# Connectors.net
KiCad netlist of a schematic drawn in Altium Designer
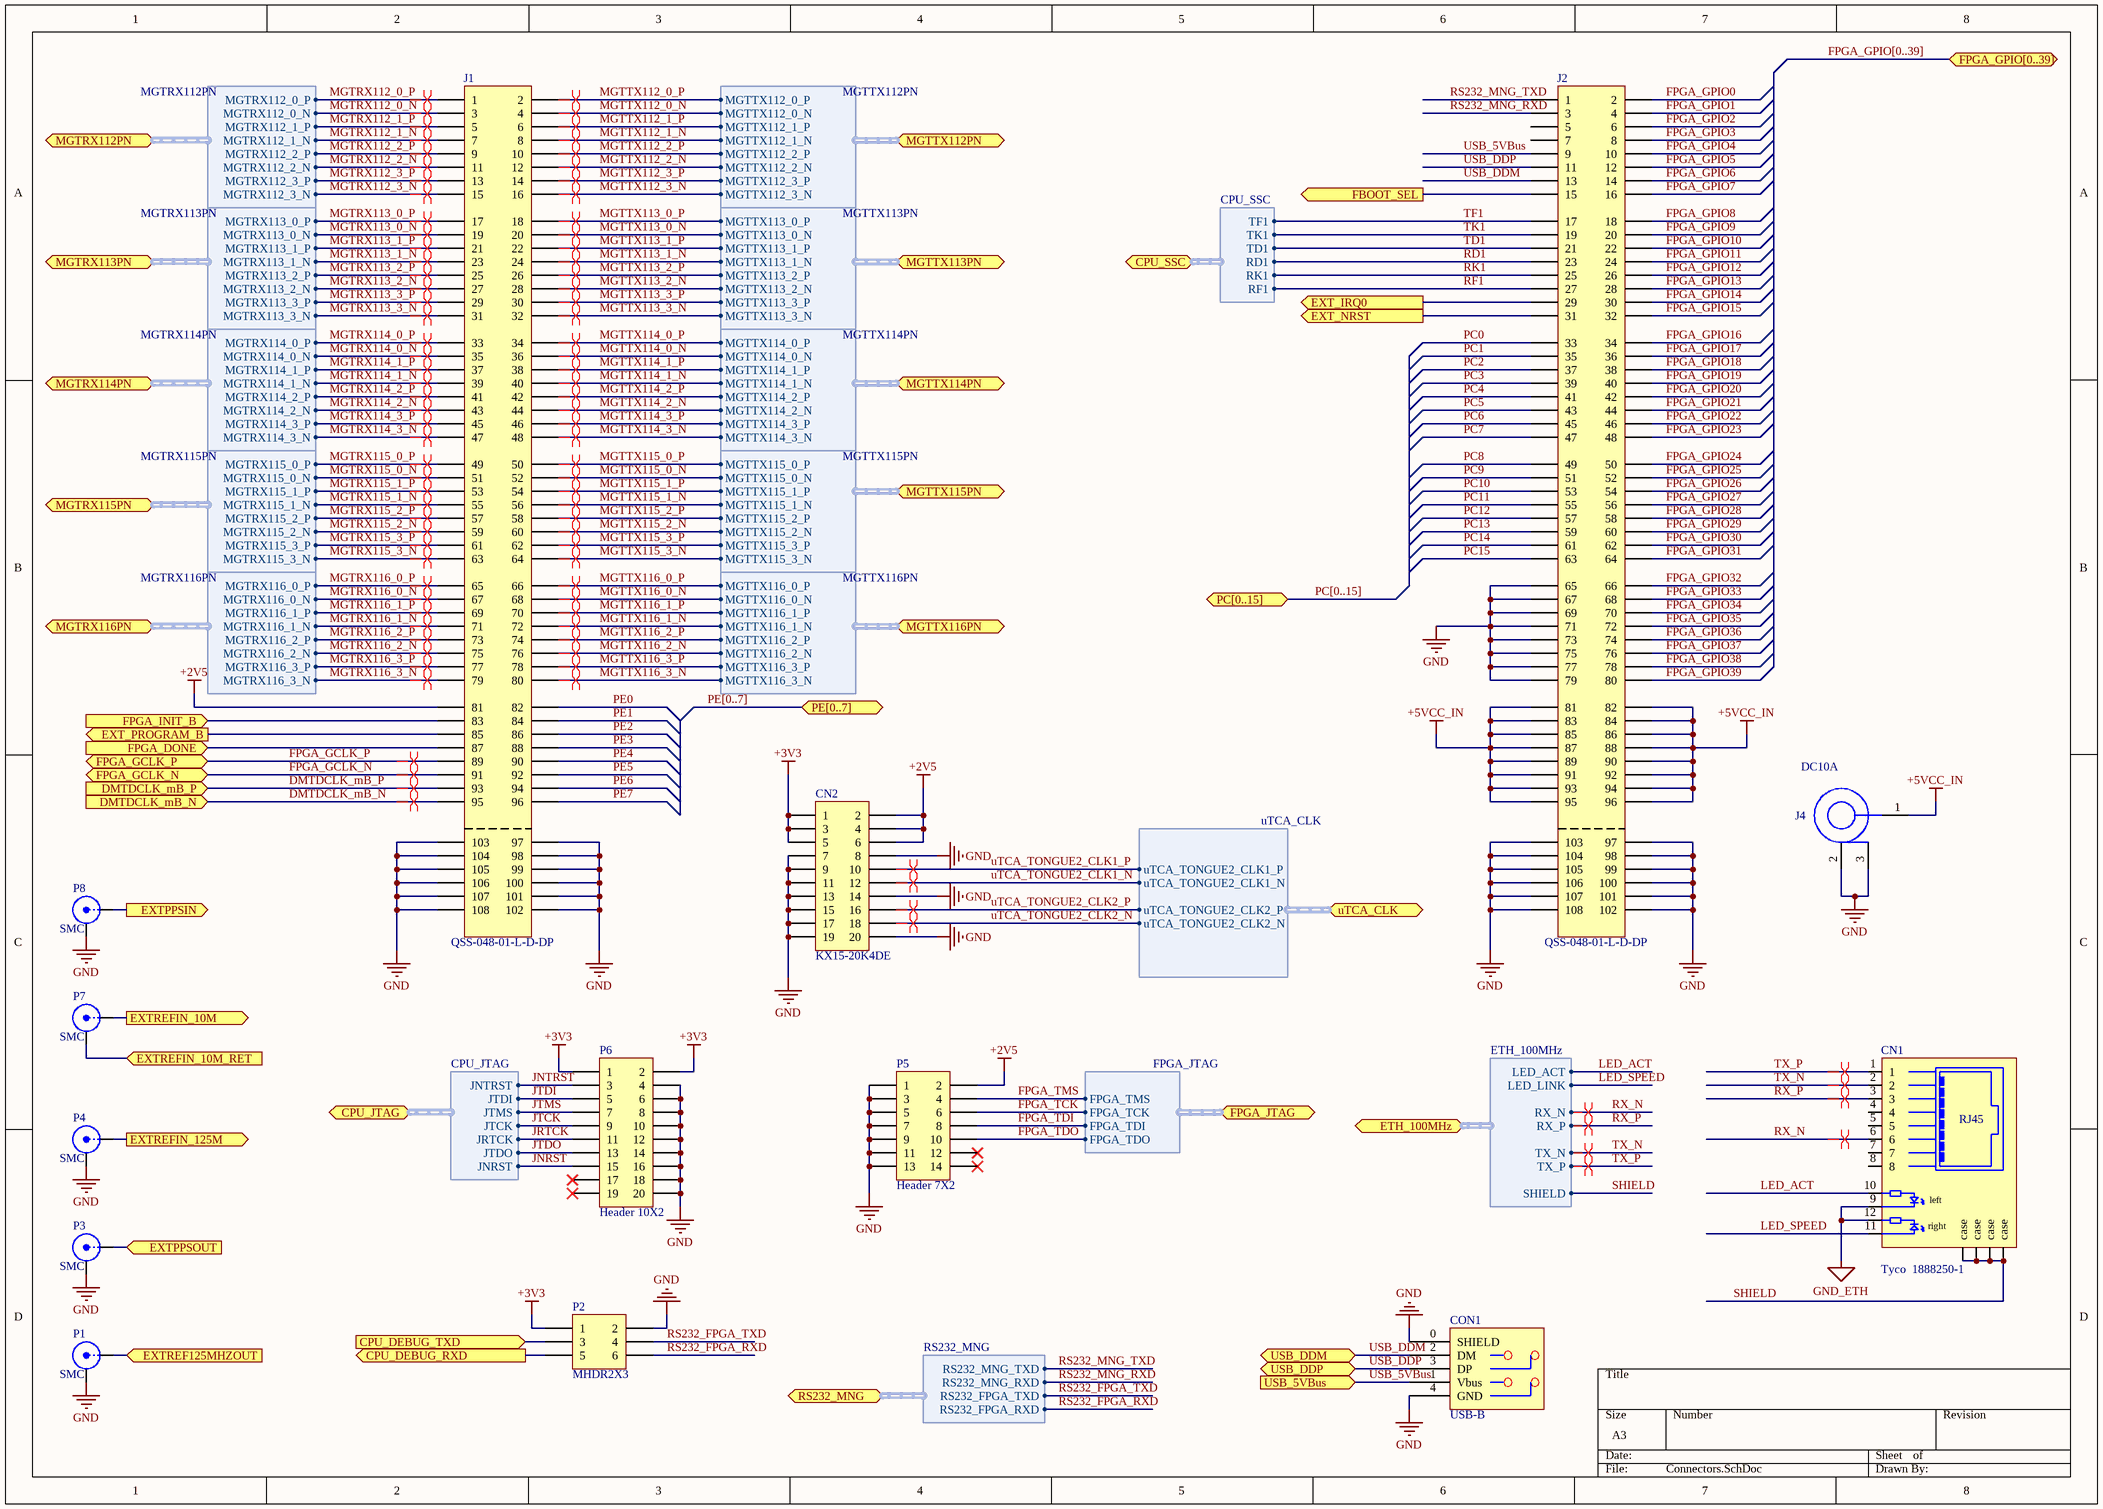
[diagram p0: Connectors.SchDoc]

(export (version "E")
  (design (tool "Eeschema 10.0.6"))
  (components
    (comp (ref "CN1")
      (value "Tyco  1888250-1")
      (footprint "TYCO_ETHERNET_1888250-1")
      (description "low profile uTCA Ethernet jack (RJ45)")
      (libsource (lib "wr_switch") (part "CON_ETHERNET_TYCO_1888250-1"))
    )
    (comp (ref "CN2")
      (value "KX15-20K4DE")
      (footprint "JAE_KX15_20P")
      (description "multipin B2B connector (plug)")
      (libsource (lib "wr_switch") (part "KX15_20p"))
    )
    (comp (ref "CON1")
      (value "USB-B")
      (footprint "USBB-G")
      (description "USB Receptacle Type B Right Angle")
      (libsource (lib "wr_switch") (part "CON_USB_B"))
    )
    (comp (ref "J1")
      (value "QSS-048-01-L-D-DP")
      (footprint "QSS-048-01-X-D-DP-A")
      (libsource (lib "wr_switch") (part "QSS-048-01-L-D-DP"))
    )
    (comp (ref "J2")
      (value "QSS-048-01-L-D-DP")
      (footprint "QSS-048-01-X-D-DP-A")
      (libsource (lib "wr_switch") (part "QSS-048-01-L-D-DP"))
    )
    (comp (ref "J4")
      (value "DC10A")
      (footprint "dc-10")
      (description "Power Jack 5A @ 12V")
      (libsource (lib "wr_switch") (part "PWR_JACK"))
    )
    (comp (ref "P1")
      (value "SMC")
      (footprint "SMB_V-RJ45")
      (description "SMB Straight Connector")
      (fields (field (name "PUBLISHER") "Altium Limited"))
      (libsource (lib "Miscellaneous Connectors") (part "SMB"))
    )
    (comp (ref "P2")
      (value "MHDR2X3")
      (footprint "HDR2X3")
      (description "Header, 3-Pin, Dual row, 2.54mm pitch")
      (fields (field (name "PUBLISHER") "Altium Limited"))
      (libsource (lib "Miscellaneous Connectors") (part "MHDR2X3"))
    )
    (comp (ref "P3")
      (value "SMC")
      (footprint "SMB_V-RJ45")
      (description "SMB Straight Connector")
      (fields (field (name "PUBLISHER") "Altium Limited"))
      (libsource (lib "Miscellaneous Connectors") (part "SMB"))
    )
    (comp (ref "P4")
      (value "SMC")
      (footprint "SMB_V-RJ45")
      (description "SMB Straight Connector")
      (fields (field (name "PUBLISHER") "Altium Limited"))
      (libsource (lib "Miscellaneous Connectors") (part "SMB"))
    )
    (comp (ref "P5")
      (value "Header 7X2")
      (footprint "CONN_HDR_SMD_2mm_2x7")
      (description "Header, 7-Pin, Dual row, 2.0 mm pitch")
      (fields (field (name "PUBLISHER") "Altium Limited"))
      (libsource (lib "Miscellaneous Connectors") (part "Header 7X2"))
    )
    (comp (ref "P6")
      (value "Header 10X2")
      (footprint "HDR2X10")
      (description "Header, 10-Pin, Dual row, 2.54mm pitch")
      (fields (field (name "MANUFACTURER") "Sullis Connectors") (field (name "PUBLISHER") "Altium Limited"))
      (libsource (lib "Miscellaneous Connectors") (part "Header 10X2"))
    )
    (comp (ref "P7")
      (value "SMC")
      (footprint "SMB_V-RJ45")
      (description "SMB Straight Connector")
      (fields (field (name "PUBLISHER") "Altium Limited"))
      (libsource (lib "Miscellaneous Connectors") (part "SMB"))
    )
    (comp (ref "P8")
      (value "SMC")
      (footprint "SMB_V-RJ45")
      (description "SMB Straight Connector")
      (fields (field (name "PUBLISHER") "Altium Limited"))
      (libsource (lib "Miscellaneous Connectors") (part "SMB"))
    )
  )
  (nets
    (net (code "17") (name "+2V5") (class "Default")
      (node (ref "CN2") (pin "2") (pinfunction "2_2") (pintype "passive"))
      (node (ref "CN2") (pin "4") (pinfunction "4_4") (pintype "passive"))
      (node (ref "CN2") (pin "6") (pinfunction "6_6") (pintype "passive"))
      (node (ref "J1") (pin "81") (pinfunction "81_81") (pintype "passive"))
      (node (ref "P5") (pin "2") (pinfunction "2_2") (pintype "passive"))
    )
    (net (code "18") (name "+3V3") (class "Default")
      (node (ref "CN2") (pin "1") (pinfunction "1_1") (pintype "passive"))
      (node (ref "CN2") (pin "3") (pinfunction "3_3") (pintype "passive"))
      (node (ref "CN2") (pin "5") (pinfunction "5_5") (pintype "passive"))
      (node (ref "P2") (pin "1") (pinfunction "1_1") (pintype "passive"))
      (node (ref "P6") (pin "1") (pinfunction "1_1") (pintype "passive"))
      (node (ref "P6") (pin "2") (pinfunction "2_2") (pintype "passive"))
    )
    (net (code "19") (name "+5VCC_IN") (class "Default")
      (node (ref "J2") (pin "81") (pinfunction "81_81") (pintype "passive"))
      (node (ref "J2") (pin "82") (pinfunction "82_82") (pintype "passive"))
      (node (ref "J2") (pin "83") (pinfunction "83_83") (pintype "passive"))
      (node (ref "J2") (pin "84") (pinfunction "84_84") (pintype "passive"))
      (node (ref "J2") (pin "85") (pinfunction "85_85") (pintype "passive"))
      (node (ref "J2") (pin "86") (pinfunction "86_86") (pintype "passive"))
      (node (ref "J2") (pin "87") (pinfunction "87_87") (pintype "passive"))
      (node (ref "J2") (pin "88") (pinfunction "88_88") (pintype "passive"))
      (node (ref "J2") (pin "89") (pinfunction "89_89") (pintype "passive"))
      (node (ref "J2") (pin "90") (pinfunction "90_90") (pintype "passive"))
      (node (ref "J2") (pin "91") (pinfunction "91_91") (pintype "passive"))
      (node (ref "J2") (pin "92") (pinfunction "92_92") (pintype "passive"))
      (node (ref "J2") (pin "93") (pinfunction "93_93") (pintype "passive"))
      (node (ref "J2") (pin "94") (pinfunction "94_94") (pintype "passive"))
      (node (ref "J2") (pin "95") (pinfunction "95_95") (pintype "passive"))
      (node (ref "J2") (pin "96") (pinfunction "96_96") (pintype "passive"))
      (node (ref "J4") (pin "1") (pinfunction "P1_1") (pintype "power_in"))
    )
    (net (code "20") (name "/CPU_DEBUG_RXD") (class "Default")
      (node (ref "P2") (pin "5") (pinfunction "5_5") (pintype "passive"))
    )
    (net (code "21") (name "/CPU_DEBUG_TXD") (class "Default")
      (node (ref "P2") (pin "3") (pinfunction "3_3") (pintype "passive"))
    )
    (net (code "22") (name "/DMTDCLK_mB_N") (class "Default")
      (node (ref "J1") (pin "95") (pinfunction "95_95") (pintype "passive"))
    )
    (net (code "23") (name "/DMTDCLK_mB_P") (class "Default")
      (node (ref "J1") (pin "93") (pinfunction "93_93") (pintype "passive"))
    )
    (net (code "24") (name "/EXTPPSIN") (class "Default")
      (node (ref "P8") (pin "1") (pinfunction "X_1") (pintype "passive"))
    )
    (net (code "25") (name "/EXTPPSOUT") (class "Default")
      (node (ref "P3") (pin "1") (pinfunction "X_1") (pintype "passive"))
    )
    (net (code "26") (name "/EXTREF125MHZOUT") (class "Default")
      (node (ref "P1") (pin "1") (pinfunction "X_1") (pintype "passive"))
    )
    (net (code "27") (name "/EXTREFIN_10M") (class "Default")
      (node (ref "P7") (pin "1") (pinfunction "X_1") (pintype "passive"))
    )
    (net (code "28") (name "/EXTREFIN_10M_RET") (class "Default")
      (node (ref "P7") (pin "2") (pinfunction "Y_2") (pintype "passive"))
    )
    (net (code "29") (name "/EXTREFIN_125M") (class "Default")
      (node (ref "P4") (pin "1") (pinfunction "X_1") (pintype "passive"))
    )
    (net (code "30") (name "/EXT_IRQ0") (class "Default")
      (node (ref "J2") (pin "29") (pinfunction "29_29") (pintype "passive"))
    )
    (net (code "31") (name "/EXT_NRST") (class "Default")
      (node (ref "J2") (pin "31") (pinfunction "31_31") (pintype "passive"))
    )
    (net (code "32") (name "/EXT_PROGRAM_B") (class "Default")
      (node (ref "J1") (pin "85") (pinfunction "85_85") (pintype "passive"))
    )
    (net (code "33") (name "/FBOOT_SEL") (class "Default")
      (node (ref "J2") (pin "15") (pinfunction "15_15") (pintype "passive"))
    )
    (net (code "34") (name "/FPGA_DONE") (class "Default")
      (node (ref "J1") (pin "87") (pinfunction "87_87") (pintype "passive"))
    )
    (net (code "35") (name "/FPGA_GCLK_N") (class "Default")
      (node (ref "J1") (pin "91") (pinfunction "91_91") (pintype "passive"))
    )
    (net (code "36") (name "/FPGA_GCLK_P") (class "Default")
      (node (ref "J1") (pin "89") (pinfunction "89_89") (pintype "passive"))
    )
    (net (code "37") (name "/FPGA_GPIO0") (class "Default")
      (node (ref "J2") (pin "2") (pinfunction "2_2") (pintype "passive"))
    )
    (net (code "38") (name "/FPGA_GPIO1") (class "Default")
      (node (ref "J2") (pin "4") (pinfunction "4_4") (pintype "passive"))
    )
    (net (code "39") (name "/FPGA_GPIO2") (class "Default")
      (node (ref "J2") (pin "6") (pinfunction "6_6") (pintype "passive"))
    )
    (net (code "40") (name "/FPGA_GPIO3") (class "Default")
      (node (ref "J2") (pin "8") (pinfunction "8_8") (pintype "passive"))
    )
    (net (code "41") (name "/FPGA_GPIO4") (class "Default")
      (node (ref "J2") (pin "10") (pinfunction "10_10") (pintype "passive"))
    )
    (net (code "42") (name "/FPGA_GPIO5") (class "Default")
      (node (ref "J2") (pin "12") (pinfunction "12_12") (pintype "passive"))
    )
    (net (code "43") (name "/FPGA_GPIO6") (class "Default")
      (node (ref "J2") (pin "14") (pinfunction "14_14") (pintype "passive"))
    )
    (net (code "44") (name "/FPGA_GPIO7") (class "Default")
      (node (ref "J2") (pin "16") (pinfunction "16_16") (pintype "passive"))
    )
    (net (code "45") (name "/FPGA_GPIO8") (class "Default")
      (node (ref "J2") (pin "18") (pinfunction "18_18") (pintype "passive"))
    )
    (net (code "46") (name "/FPGA_GPIO9") (class "Default")
      (node (ref "J2") (pin "20") (pinfunction "20_20") (pintype "passive"))
    )
    (net (code "47") (name "/FPGA_GPIO10") (class "Default")
      (node (ref "J2") (pin "22") (pinfunction "22_22") (pintype "passive"))
    )
    (net (code "48") (name "/FPGA_GPIO11") (class "Default")
      (node (ref "J2") (pin "24") (pinfunction "24_24") (pintype "passive"))
    )
    (net (code "49") (name "/FPGA_GPIO12") (class "Default")
      (node (ref "J2") (pin "26") (pinfunction "26_26") (pintype "passive"))
    )
    (net (code "50") (name "/FPGA_GPIO13") (class "Default")
      (node (ref "J2") (pin "28") (pinfunction "28_28") (pintype "passive"))
    )
    (net (code "51") (name "/FPGA_GPIO14") (class "Default")
      (node (ref "J2") (pin "30") (pinfunction "30_30") (pintype "passive"))
    )
    (net (code "52") (name "/FPGA_GPIO15") (class "Default")
      (node (ref "J2") (pin "32") (pinfunction "32_32") (pintype "passive"))
    )
    (net (code "53") (name "/FPGA_GPIO16") (class "Default")
      (node (ref "J2") (pin "34") (pinfunction "34_34") (pintype "passive"))
    )
    (net (code "54") (name "/FPGA_GPIO17") (class "Default")
      (node (ref "J2") (pin "36") (pinfunction "36_36") (pintype "passive"))
    )
    (net (code "55") (name "/FPGA_GPIO18") (class "Default")
      (node (ref "J2") (pin "38") (pinfunction "38_38") (pintype "passive"))
    )
    (net (code "56") (name "/FPGA_GPIO19") (class "Default")
      (node (ref "J2") (pin "40") (pinfunction "40_40") (pintype "passive"))
    )
    (net (code "57") (name "/FPGA_GPIO20") (class "Default")
      (node (ref "J2") (pin "42") (pinfunction "42_42") (pintype "passive"))
    )
    (net (code "58") (name "/FPGA_GPIO21") (class "Default")
      (node (ref "J2") (pin "44") (pinfunction "44_44") (pintype "passive"))
    )
    (net (code "59") (name "/FPGA_GPIO22") (class "Default")
      (node (ref "J2") (pin "46") (pinfunction "46_46") (pintype "passive"))
    )
    (net (code "60") (name "/FPGA_GPIO23") (class "Default")
      (node (ref "J2") (pin "48") (pinfunction "48_48") (pintype "passive"))
    )
    (net (code "61") (name "/FPGA_GPIO24") (class "Default")
      (node (ref "J2") (pin "50") (pinfunction "50_50") (pintype "passive"))
    )
    (net (code "62") (name "/FPGA_GPIO25") (class "Default")
      (node (ref "J2") (pin "52") (pinfunction "52_52") (pintype "passive"))
    )
    (net (code "63") (name "/FPGA_GPIO26") (class "Default")
      (node (ref "J2") (pin "54") (pinfunction "54_54") (pintype "passive"))
    )
    (net (code "64") (name "/FPGA_GPIO27") (class "Default")
      (node (ref "J2") (pin "56") (pinfunction "56_56") (pintype "passive"))
    )
    (net (code "65") (name "/FPGA_GPIO28") (class "Default")
      (node (ref "J2") (pin "58") (pinfunction "58_58") (pintype "passive"))
    )
    (net (code "66") (name "/FPGA_GPIO29") (class "Default")
      (node (ref "J2") (pin "60") (pinfunction "60_60") (pintype "passive"))
    )
    (net (code "67") (name "/FPGA_GPIO30") (class "Default")
      (node (ref "J2") (pin "62") (pinfunction "62_62") (pintype "passive"))
    )
    (net (code "68") (name "/FPGA_GPIO31") (class "Default")
      (node (ref "J2") (pin "64") (pinfunction "64_64") (pintype "passive"))
    )
    (net (code "69") (name "/FPGA_GPIO32") (class "Default")
      (node (ref "J2") (pin "66") (pinfunction "66_66") (pintype "passive"))
    )
    (net (code "70") (name "/FPGA_GPIO33") (class "Default")
      (node (ref "J2") (pin "68") (pinfunction "68_68") (pintype "passive"))
    )
    (net (code "71") (name "/FPGA_GPIO34") (class "Default")
      (node (ref "J2") (pin "70") (pinfunction "70_70") (pintype "passive"))
    )
    (net (code "72") (name "/FPGA_GPIO35") (class "Default")
      (node (ref "J2") (pin "72") (pinfunction "72_72") (pintype "passive"))
    )
    (net (code "73") (name "/FPGA_GPIO36") (class "Default")
      (node (ref "J2") (pin "74") (pinfunction "74_74") (pintype "passive"))
    )
    (net (code "74") (name "/FPGA_GPIO37") (class "Default")
      (node (ref "J2") (pin "76") (pinfunction "76_76") (pintype "passive"))
    )
    (net (code "75") (name "/FPGA_GPIO38") (class "Default")
      (node (ref "J2") (pin "78") (pinfunction "78_78") (pintype "passive"))
    )
    (net (code "76") (name "/FPGA_GPIO39") (class "Default")
      (node (ref "J2") (pin "80") (pinfunction "80_80") (pintype "passive"))
    )
    (net (code "78") (name "/FPGA_INIT_B") (class "Default")
      (node (ref "J1") (pin "83") (pinfunction "83_83") (pintype "passive"))
    )
    (net (code "79") (name "/FPGA_TCK") (class "Default")
      (node (ref "P5") (pin "6") (pinfunction "6_6") (pintype "passive"))
    )
    (net (code "80") (name "/FPGA_TDI") (class "Default")
      (node (ref "P5") (pin "8") (pinfunction "8_8") (pintype "passive"))
    )
    (net (code "81") (name "/FPGA_TDO") (class "Default")
      (node (ref "P5") (pin "10") (pinfunction "10_10") (pintype "passive"))
    )
    (net (code "82") (name "/FPGA_TMS") (class "Default")
      (node (ref "P5") (pin "4") (pinfunction "4_4") (pintype "passive"))
    )
    (net (code "83") (name "/JNRST") (class "Default")
      (node (ref "P6") (pin "15") (pinfunction "15_15") (pintype "passive"))
    )
    (net (code "84") (name "/JNTRST") (class "Default")
      (node (ref "P6") (pin "3") (pinfunction "3_3") (pintype "passive"))
    )
    (net (code "85") (name "/JRTCK") (class "Default")
      (node (ref "P6") (pin "11") (pinfunction "11_11") (pintype "passive"))
    )
    (net (code "86") (name "/JTCK") (class "Default")
      (node (ref "P6") (pin "9") (pinfunction "9_9") (pintype "passive"))
    )
    (net (code "87") (name "/JTDI") (class "Default")
      (node (ref "P6") (pin "5") (pinfunction "5_5") (pintype "passive"))
    )
    (net (code "88") (name "/JTDO") (class "Default")
      (node (ref "P6") (pin "13") (pinfunction "13_13") (pintype "passive"))
    )
    (net (code "89") (name "/JTMS") (class "Default")
      (node (ref "P6") (pin "7") (pinfunction "7_7") (pintype "passive"))
    )
    (net (code "90") (name "/LED_ACT") (class "Default")
      (node (ref "CN1") (pin "10") (pinfunction "D1_10") (pintype "passive"))
    )
    (net (code "91") (name "/LED_SPEED") (class "Default")
      (node (ref "CN1") (pin "11") (pinfunction "D4_11") (pintype "passive"))
    )
    (net (code "92") (name "/MGTRX112_0_N") (class "Default")
      (node (ref "J1") (pin "3") (pinfunction "3_3") (pintype "passive"))
    )
    (net (code "93") (name "/MGTRX112_0_P") (class "Default")
      (node (ref "J1") (pin "1") (pinfunction "1_1") (pintype "passive"))
    )
    (net (code "94") (name "/MGTRX112_1_N") (class "Default")
      (node (ref "J1") (pin "7") (pinfunction "7_7") (pintype "passive"))
    )
    (net (code "95") (name "/MGTRX112_1_P") (class "Default")
      (node (ref "J1") (pin "5") (pinfunction "5_5") (pintype "passive"))
    )
    (net (code "96") (name "/MGTRX112_2_N") (class "Default")
      (node (ref "J1") (pin "11") (pinfunction "11_11") (pintype "passive"))
    )
    (net (code "97") (name "/MGTRX112_2_P") (class "Default")
      (node (ref "J1") (pin "9") (pinfunction "9_9") (pintype "passive"))
    )
    (net (code "98") (name "/MGTRX112_3_N") (class "Default")
      (node (ref "J1") (pin "15") (pinfunction "15_15") (pintype "passive"))
    )
    (net (code "99") (name "/MGTRX112_3_P") (class "Default")
      (node (ref "J1") (pin "13") (pinfunction "13_13") (pintype "passive"))
    )
    (net (code "100") (name "/MGTRX113_0_N") (class "Default")
      (node (ref "J1") (pin "19") (pinfunction "19_19") (pintype "passive"))
    )
    (net (code "101") (name "/MGTRX113_0_P") (class "Default")
      (node (ref "J1") (pin "17") (pinfunction "17_17") (pintype "passive"))
    )
    (net (code "102") (name "/MGTRX113_1_N") (class "Default")
      (node (ref "J1") (pin "23") (pinfunction "23_23") (pintype "passive"))
    )
    (net (code "103") (name "/MGTRX113_1_P") (class "Default")
      (node (ref "J1") (pin "21") (pinfunction "21_21") (pintype "passive"))
    )
    (net (code "104") (name "/MGTRX113_2_N") (class "Default")
      (node (ref "J1") (pin "27") (pinfunction "27_27") (pintype "passive"))
    )
    (net (code "105") (name "/MGTRX113_2_P") (class "Default")
      (node (ref "J1") (pin "25") (pinfunction "25_25") (pintype "passive"))
    )
    (net (code "106") (name "/MGTRX113_3_N") (class "Default")
      (node (ref "J1") (pin "31") (pinfunction "31_31") (pintype "passive"))
    )
    (net (code "107") (name "/MGTRX113_3_P") (class "Default")
      (node (ref "J1") (pin "29") (pinfunction "29_29") (pintype "passive"))
    )
    (net (code "108") (name "/MGTRX114_0_N") (class "Default")
      (node (ref "J1") (pin "35") (pinfunction "35_35") (pintype "passive"))
    )
    (net (code "109") (name "/MGTRX114_0_P") (class "Default")
      (node (ref "J1") (pin "33") (pinfunction "33_33") (pintype "passive"))
    )
    (net (code "110") (name "/MGTRX114_1_N") (class "Default")
      (node (ref "J1") (pin "39") (pinfunction "39_39") (pintype "passive"))
    )
    (net (code "111") (name "/MGTRX114_1_P") (class "Default")
      (node (ref "J1") (pin "37") (pinfunction "37_37") (pintype "passive"))
    )
    (net (code "112") (name "/MGTRX114_2_N") (class "Default")
      (node (ref "J1") (pin "43") (pinfunction "43_43") (pintype "passive"))
    )
    (net (code "113") (name "/MGTRX114_2_P") (class "Default")
      (node (ref "J1") (pin "41") (pinfunction "41_41") (pintype "passive"))
    )
    (net (code "114") (name "/MGTRX114_3_N") (class "Default")
      (node (ref "J1") (pin "47") (pinfunction "47_47") (pintype "passive"))
    )
    (net (code "115") (name "/MGTRX114_3_P") (class "Default")
      (node (ref "J1") (pin "45") (pinfunction "45_45") (pintype "passive"))
    )
    (net (code "116") (name "/MGTRX115_0_N") (class "Default")
      (node (ref "J1") (pin "51") (pinfunction "51_51") (pintype "passive"))
    )
    (net (code "117") (name "/MGTRX115_0_P") (class "Default")
      (node (ref "J1") (pin "49") (pinfunction "49_49") (pintype "passive"))
    )
    (net (code "118") (name "/MGTRX115_1_N") (class "Default")
      (node (ref "J1") (pin "55") (pinfunction "55_55") (pintype "passive"))
    )
    (net (code "119") (name "/MGTRX115_1_P") (class "Default")
      (node (ref "J1") (pin "53") (pinfunction "53_53") (pintype "passive"))
    )
    (net (code "120") (name "/MGTRX115_2_N") (class "Default")
      (node (ref "J1") (pin "59") (pinfunction "59_59") (pintype "passive"))
    )
    (net (code "121") (name "/MGTRX115_2_P") (class "Default")
      (node (ref "J1") (pin "57") (pinfunction "57_57") (pintype "passive"))
    )
    (net (code "122") (name "/MGTRX115_3_N") (class "Default")
      (node (ref "J1") (pin "63") (pinfunction "63_63") (pintype "passive"))
    )
    (net (code "123") (name "/MGTRX115_3_P") (class "Default")
      (node (ref "J1") (pin "61") (pinfunction "61_61") (pintype "passive"))
    )
    (net (code "124") (name "/MGTRX116_0_N") (class "Default")
      (node (ref "J1") (pin "67") (pinfunction "67_67") (pintype "passive"))
    )
    (net (code "125") (name "/MGTRX116_0_P") (class "Default")
      (node (ref "J1") (pin "65") (pinfunction "65_65") (pintype "passive"))
    )
    (net (code "126") (name "/MGTRX116_1_N") (class "Default")
      (node (ref "J1") (pin "71") (pinfunction "71_71") (pintype "passive"))
    )
    (net (code "127") (name "/MGTRX116_1_P") (class "Default")
      (node (ref "J1") (pin "69") (pinfunction "69_69") (pintype "passive"))
    )
    (net (code "128") (name "/MGTRX116_2_N") (class "Default")
      (node (ref "J1") (pin "75") (pinfunction "75_75") (pintype "passive"))
    )
    (net (code "129") (name "/MGTRX116_2_P") (class "Default")
      (node (ref "J1") (pin "73") (pinfunction "73_73") (pintype "passive"))
    )
    (net (code "130") (name "/MGTRX116_3_N") (class "Default")
      (node (ref "J1") (pin "79") (pinfunction "79_79") (pintype "passive"))
    )
    (net (code "131") (name "/MGTRX116_3_P") (class "Default")
      (node (ref "J1") (pin "77") (pinfunction "77_77") (pintype "passive"))
    )
    (net (code "133") (name "/MGTTX112_0_N") (class "Default")
      (node (ref "J1") (pin "4") (pinfunction "4_4") (pintype "passive"))
    )
    (net (code "134") (name "/MGTTX112_0_P") (class "Default")
      (node (ref "J1") (pin "2") (pinfunction "2_2") (pintype "passive"))
    )
    (net (code "135") (name "/MGTTX112_1_N") (class "Default")
      (node (ref "J1") (pin "8") (pinfunction "8_8") (pintype "passive"))
    )
    (net (code "136") (name "/MGTTX112_1_P") (class "Default")
      (node (ref "J1") (pin "6") (pinfunction "6_6") (pintype "passive"))
    )
    (net (code "137") (name "/MGTTX112_2_N") (class "Default")
      (node (ref "J1") (pin "12") (pinfunction "12_12") (pintype "passive"))
    )
    (net (code "138") (name "/MGTTX112_2_P") (class "Default")
      (node (ref "J1") (pin "10") (pinfunction "10_10") (pintype "passive"))
    )
    (net (code "139") (name "/MGTTX112_3_N") (class "Default")
      (node (ref "J1") (pin "16") (pinfunction "16_16") (pintype "passive"))
    )
    (net (code "140") (name "/MGTTX112_3_P") (class "Default")
      (node (ref "J1") (pin "14") (pinfunction "14_14") (pintype "passive"))
    )
    (net (code "141") (name "/MGTTX113_0_N") (class "Default")
      (node (ref "J1") (pin "20") (pinfunction "20_20") (pintype "passive"))
    )
    (net (code "142") (name "/MGTTX113_0_P") (class "Default")
      (node (ref "J1") (pin "18") (pinfunction "18_18") (pintype "passive"))
    )
    (net (code "143") (name "/MGTTX113_1_N") (class "Default")
      (node (ref "J1") (pin "24") (pinfunction "24_24") (pintype "passive"))
    )
    (net (code "144") (name "/MGTTX113_1_P") (class "Default")
      (node (ref "J1") (pin "22") (pinfunction "22_22") (pintype "passive"))
    )
    (net (code "145") (name "/MGTTX113_2_N") (class "Default")
      (node (ref "J1") (pin "28") (pinfunction "28_28") (pintype "passive"))
    )
    (net (code "146") (name "/MGTTX113_2_P") (class "Default")
      (node (ref "J1") (pin "26") (pinfunction "26_26") (pintype "passive"))
    )
    (net (code "147") (name "/MGTTX113_3_N") (class "Default")
      (node (ref "J1") (pin "32") (pinfunction "32_32") (pintype "passive"))
    )
    (net (code "148") (name "/MGTTX113_3_P") (class "Default")
      (node (ref "J1") (pin "30") (pinfunction "30_30") (pintype "passive"))
    )
    (net (code "149") (name "/MGTTX114_0_N") (class "Default")
      (node (ref "J1") (pin "36") (pinfunction "36_36") (pintype "passive"))
    )
    (net (code "150") (name "/MGTTX114_0_P") (class "Default")
      (node (ref "J1") (pin "34") (pinfunction "34_34") (pintype "passive"))
    )
    (net (code "151") (name "/MGTTX114_1_N") (class "Default")
      (node (ref "J1") (pin "40") (pinfunction "40_40") (pintype "passive"))
    )
    (net (code "152") (name "/MGTTX114_1_P") (class "Default")
      (node (ref "J1") (pin "38") (pinfunction "38_38") (pintype "passive"))
    )
    (net (code "153") (name "/MGTTX114_2_N") (class "Default")
      (node (ref "J1") (pin "44") (pinfunction "44_44") (pintype "passive"))
    )
    (net (code "154") (name "/MGTTX114_2_P") (class "Default")
      (node (ref "J1") (pin "42") (pinfunction "42_42") (pintype "passive"))
    )
    (net (code "155") (name "/MGTTX114_3_N") (class "Default")
      (node (ref "J1") (pin "48") (pinfunction "48_48") (pintype "passive"))
    )
    (net (code "156") (name "/MGTTX114_3_P") (class "Default")
      (node (ref "J1") (pin "46") (pinfunction "46_46") (pintype "passive"))
    )
    (net (code "157") (name "/MGTTX115_0_N") (class "Default")
      (node (ref "J1") (pin "52") (pinfunction "52_52") (pintype "passive"))
    )
    (net (code "158") (name "/MGTTX115_0_P") (class "Default")
      (node (ref "J1") (pin "50") (pinfunction "50_50") (pintype "passive"))
    )
    (net (code "159") (name "/MGTTX115_1_N") (class "Default")
      (node (ref "J1") (pin "56") (pinfunction "56_56") (pintype "passive"))
    )
    (net (code "160") (name "/MGTTX115_1_P") (class "Default")
      (node (ref "J1") (pin "54") (pinfunction "54_54") (pintype "passive"))
    )
    (net (code "161") (name "/MGTTX115_2_N") (class "Default")
      (node (ref "J1") (pin "60") (pinfunction "60_60") (pintype "passive"))
    )
    (net (code "162") (name "/MGTTX115_2_P") (class "Default")
      (node (ref "J1") (pin "58") (pinfunction "58_58") (pintype "passive"))
    )
    (net (code "163") (name "/MGTTX115_3_N") (class "Default")
      (node (ref "J1") (pin "64") (pinfunction "64_64") (pintype "passive"))
    )
    (net (code "164") (name "/MGTTX115_3_P") (class "Default")
      (node (ref "J1") (pin "62") (pinfunction "62_62") (pintype "passive"))
    )
    (net (code "165") (name "/MGTTX116_0_N") (class "Default")
      (node (ref "J1") (pin "68") (pinfunction "68_68") (pintype "passive"))
    )
    (net (code "166") (name "/MGTTX116_0_P") (class "Default")
      (node (ref "J1") (pin "66") (pinfunction "66_66") (pintype "passive"))
    )
    (net (code "167") (name "/MGTTX116_1_N") (class "Default")
      (node (ref "J1") (pin "72") (pinfunction "72_72") (pintype "passive"))
    )
    (net (code "168") (name "/MGTTX116_1_P") (class "Default")
      (node (ref "J1") (pin "70") (pinfunction "70_70") (pintype "passive"))
    )
    (net (code "169") (name "/MGTTX116_2_N") (class "Default")
      (node (ref "J1") (pin "76") (pinfunction "76_76") (pintype "passive"))
    )
    (net (code "170") (name "/MGTTX116_2_P") (class "Default")
      (node (ref "J1") (pin "74") (pinfunction "74_74") (pintype "passive"))
    )
    (net (code "171") (name "/MGTTX116_3_N") (class "Default")
      (node (ref "J1") (pin "80") (pinfunction "80_80") (pintype "passive"))
    )
    (net (code "172") (name "/MGTTX116_3_P") (class "Default")
      (node (ref "J1") (pin "78") (pinfunction "78_78") (pintype "passive"))
    )
    (net (code "173") (name "/PC0") (class "Default")
      (node (ref "J2") (pin "33") (pinfunction "33_33") (pintype "passive"))
    )
    (net (code "174") (name "/PC1") (class "Default")
      (node (ref "J2") (pin "35") (pinfunction "35_35") (pintype "passive"))
    )
    (net (code "175") (name "/PC2") (class "Default")
      (node (ref "J2") (pin "37") (pinfunction "37_37") (pintype "passive"))
    )
    (net (code "176") (name "/PC3") (class "Default")
      (node (ref "J2") (pin "39") (pinfunction "39_39") (pintype "passive"))
    )
    (net (code "177") (name "/PC4") (class "Default")
      (node (ref "J2") (pin "41") (pinfunction "41_41") (pintype "passive"))
    )
    (net (code "178") (name "/PC5") (class "Default")
      (node (ref "J2") (pin "43") (pinfunction "43_43") (pintype "passive"))
    )
    (net (code "179") (name "/PC6") (class "Default")
      (node (ref "J2") (pin "45") (pinfunction "45_45") (pintype "passive"))
    )
    (net (code "180") (name "/PC7") (class "Default")
      (node (ref "J2") (pin "47") (pinfunction "47_47") (pintype "passive"))
    )
    (net (code "181") (name "/PC8") (class "Default")
      (node (ref "J2") (pin "49") (pinfunction "49_49") (pintype "passive"))
    )
    (net (code "182") (name "/PC9") (class "Default")
      (node (ref "J2") (pin "51") (pinfunction "51_51") (pintype "passive"))
    )
    (net (code "183") (name "/PC10") (class "Default")
      (node (ref "J2") (pin "53") (pinfunction "53_53") (pintype "passive"))
    )
    (net (code "184") (name "/PC11") (class "Default")
      (node (ref "J2") (pin "55") (pinfunction "55_55") (pintype "passive"))
    )
    (net (code "185") (name "/PC12") (class "Default")
      (node (ref "J2") (pin "57") (pinfunction "57_57") (pintype "passive"))
    )
    (net (code "186") (name "/PC13") (class "Default")
      (node (ref "J2") (pin "59") (pinfunction "59_59") (pintype "passive"))
    )
    (net (code "187") (name "/PC14") (class "Default")
      (node (ref "J2") (pin "61") (pinfunction "61_61") (pintype "passive"))
    )
    (net (code "188") (name "/PC15") (class "Default")
      (node (ref "J2") (pin "63") (pinfunction "63_63") (pintype "passive"))
    )
    (net (code "190") (name "/PE0") (class "Default")
      (node (ref "J1") (pin "82") (pinfunction "82_82") (pintype "passive"))
    )
    (net (code "191") (name "/PE1") (class "Default")
      (node (ref "J1") (pin "84") (pinfunction "84_84") (pintype "passive"))
    )
    (net (code "192") (name "/PE2") (class "Default")
      (node (ref "J1") (pin "86") (pinfunction "86_86") (pintype "passive"))
    )
    (net (code "193") (name "/PE3") (class "Default")
      (node (ref "J1") (pin "88") (pinfunction "88_88") (pintype "passive"))
    )
    (net (code "194") (name "/PE4") (class "Default")
      (node (ref "J1") (pin "90") (pinfunction "90_90") (pintype "passive"))
    )
    (net (code "195") (name "/PE5") (class "Default")
      (node (ref "J1") (pin "92") (pinfunction "92_92") (pintype "passive"))
    )
    (net (code "196") (name "/PE6") (class "Default")
      (node (ref "J1") (pin "94") (pinfunction "94_94") (pintype "passive"))
    )
    (net (code "197") (name "/PE7") (class "Default")
      (node (ref "J1") (pin "96") (pinfunction "96_96") (pintype "passive"))
    )
    (net (code "199") (name "/RD1") (class "Default")
      (node (ref "J2") (pin "23") (pinfunction "23_23") (pintype "passive"))
    )
    (net (code "200") (name "/RF1") (class "Default")
      (node (ref "J2") (pin "27") (pinfunction "27_27") (pintype "passive"))
    )
    (net (code "201") (name "/RK1") (class "Default")
      (node (ref "J2") (pin "25") (pinfunction "25_25") (pintype "passive"))
    )
    (net (code "202") (name "/RS232_FPGA_RXD") (class "Default")
      (node (ref "P2") (pin "6") (pinfunction "6_6") (pintype "passive"))
    )
    (net (code "203") (name "/RS232_FPGA_TXD") (class "Default")
      (node (ref "P2") (pin "4") (pinfunction "4_4") (pintype "passive"))
    )
    (net (code "204") (name "/RS232_MNG_RXD") (class "Default")
      (node (ref "J2") (pin "3") (pinfunction "3_3") (pintype "passive"))
    )
    (net (code "205") (name "/RS232_MNG_TXD") (class "Default")
      (node (ref "J2") (pin "1") (pinfunction "1_1") (pintype "passive"))
    )
    (net (code "206") (name "/RX_N") (class "Default")
      (node (ref "CN1") (pin "6") (pinfunction "6_6") (pintype "passive"))
    )
    (net (code "207") (name "/RX_P") (class "Default")
      (node (ref "CN1") (pin "3") (pinfunction "3_3") (pintype "passive"))
    )
    (net (code "208") (name "/SHIELD") (class "Default")
      (node (ref "CN1") (pin "0") (pinfunction "case_0") (pintype "passive"))
    )
    (net (code "209") (name "/TD1") (class "Default")
      (node (ref "J2") (pin "21") (pinfunction "21_21") (pintype "passive"))
    )
    (net (code "210") (name "/TF1") (class "Default")
      (node (ref "J2") (pin "17") (pinfunction "17_17") (pintype "passive"))
    )
    (net (code "211") (name "/TK1") (class "Default")
      (node (ref "J2") (pin "19") (pinfunction "19_19") (pintype "passive"))
    )
    (net (code "212") (name "/TX_N") (class "Default")
      (node (ref "CN1") (pin "2") (pinfunction "2_2") (pintype "passive"))
    )
    (net (code "213") (name "/TX_P") (class "Default")
      (node (ref "CN1") (pin "1") (pinfunction "1_1") (pintype "passive"))
    )
    (net (code "214") (name "/USB_5VBus") (class "Default")
      (node (ref "CON1") (pin "1") (pinfunction "Vbus_1") (pintype "passive"))
      (node (ref "J2") (pin "9") (pinfunction "9_9") (pintype "passive"))
    )
    (net (code "215") (name "/USB_DDM") (class "Default")
      (node (ref "CON1") (pin "2") (pinfunction "DM_2") (pintype "passive"))
      (node (ref "J2") (pin "13") (pinfunction "13_13") (pintype "passive"))
    )
    (net (code "216") (name "/USB_DDP") (class "Default")
      (node (ref "CON1") (pin "3") (pinfunction "DP_3") (pintype "passive"))
      (node (ref "J2") (pin "11") (pinfunction "11_11") (pintype "passive"))
    )
    (net (code "217") (name "/uTCA_TONGUE2_CLK1_N") (class "Default")
      (node (ref "CN2") (pin "12") (pinfunction "12_12") (pintype "passive"))
    )
    (net (code "218") (name "/uTCA_TONGUE2_CLK1_P") (class "Default")
      (node (ref "CN2") (pin "10") (pinfunction "10_10") (pintype "passive"))
    )
    (net (code "219") (name "/uTCA_TONGUE2_CLK2_N") (class "Default")
      (node (ref "CN2") (pin "18") (pinfunction "18_18") (pintype "passive"))
    )
    (net (code "220") (name "/uTCA_TONGUE2_CLK2_P") (class "Default")
      (node (ref "CN2") (pin "16") (pinfunction "16_16") (pintype "passive"))
    )
    (net (code "236") (name "GND") (class "Default")
      (node (ref "CN2") (pin "11") (pinfunction "11_11") (pintype "passive"))
      (node (ref "CN2") (pin "13") (pinfunction "13_13") (pintype "passive"))
      (node (ref "CN2") (pin "14") (pinfunction "14_14") (pintype "passive"))
      (node (ref "CN2") (pin "15") (pinfunction "15_15") (pintype "passive"))
      (node (ref "CN2") (pin "17") (pinfunction "17_17") (pintype "passive"))
      (node (ref "CN2") (pin "19") (pinfunction "19_19") (pintype "passive"))
      (node (ref "CN2") (pin "20") (pinfunction "20_20") (pintype "passive"))
      (node (ref "CN2") (pin "7") (pinfunction "7_7") (pintype "passive"))
      (node (ref "CN2") (pin "8") (pinfunction "8_8") (pintype "passive"))
      (node (ref "CN2") (pin "9") (pinfunction "9_9") (pintype "passive"))
      (node (ref "CON1") (pin "0") (pinfunction "SHIELD_0") (pintype "passive"))
      (node (ref "CON1") (pin "4") (pinfunction "GND_4") (pintype "passive"))
      (node (ref "J1") (pin "100") (pinfunction "100_100") (pintype "passive"))
      (node (ref "J1") (pin "101") (pinfunction "101_101") (pintype "passive"))
      (node (ref "J1") (pin "102") (pinfunction "102_102") (pintype "passive"))
      (node (ref "J1") (pin "103") (pinfunction "103_103") (pintype "passive"))
      (node (ref "J1") (pin "104") (pinfunction "104_104") (pintype "passive"))
      (node (ref "J1") (pin "105") (pinfunction "105_105") (pintype "passive"))
      (node (ref "J1") (pin "106") (pinfunction "106_106") (pintype "passive"))
      (node (ref "J1") (pin "107") (pinfunction "107_107") (pintype "passive"))
      (node (ref "J1") (pin "108") (pinfunction "108_108") (pintype "passive"))
      (node (ref "J1") (pin "97") (pinfunction "97_97") (pintype "passive"))
      (node (ref "J1") (pin "98") (pinfunction "98_98") (pintype "passive"))
      (node (ref "J1") (pin "99") (pinfunction "99_99") (pintype "passive"))
      (node (ref "J2") (pin "100") (pinfunction "100_100") (pintype "passive"))
      (node (ref "J2") (pin "101") (pinfunction "101_101") (pintype "passive"))
      (node (ref "J2") (pin "102") (pinfunction "102_102") (pintype "passive"))
      (node (ref "J2") (pin "103") (pinfunction "103_103") (pintype "passive"))
      (node (ref "J2") (pin "104") (pinfunction "104_104") (pintype "passive"))
      (node (ref "J2") (pin "105") (pinfunction "105_105") (pintype "passive"))
      (node (ref "J2") (pin "106") (pinfunction "106_106") (pintype "passive"))
      (node (ref "J2") (pin "107") (pinfunction "107_107") (pintype "passive"))
      (node (ref "J2") (pin "108") (pinfunction "108_108") (pintype "passive"))
      (node (ref "J2") (pin "65") (pinfunction "65_65") (pintype "passive"))
      (node (ref "J2") (pin "67") (pinfunction "67_67") (pintype "passive"))
      (node (ref "J2") (pin "69") (pinfunction "69_69") (pintype "passive"))
      (node (ref "J2") (pin "71") (pinfunction "71_71") (pintype "passive"))
      (node (ref "J2") (pin "73") (pinfunction "73_73") (pintype "passive"))
      (node (ref "J2") (pin "75") (pinfunction "75_75") (pintype "passive"))
      (node (ref "J2") (pin "77") (pinfunction "77_77") (pintype "passive"))
      (node (ref "J2") (pin "79") (pinfunction "79_79") (pintype "passive"))
      (node (ref "J2") (pin "97") (pinfunction "97_97") (pintype "passive"))
      (node (ref "J2") (pin "98") (pinfunction "98_98") (pintype "passive"))
      (node (ref "J2") (pin "99") (pinfunction "99_99") (pintype "passive"))
      (node (ref "J4") (pin "2") (pinfunction "P2_2") (pintype "power_in"))
      (node (ref "J4") (pin "3") (pinfunction "P3_3") (pintype "power_in"))
      (node (ref "P1") (pin "2") (pinfunction "Y_2") (pintype "passive"))
      (node (ref "P2") (pin "2") (pinfunction "2_2") (pintype "passive"))
      (node (ref "P3") (pin "2") (pinfunction "Y_2") (pintype "passive"))
      (node (ref "P4") (pin "2") (pinfunction "Y_2") (pintype "passive"))
      (node (ref "P5") (pin "1") (pinfunction "1_1") (pintype "passive"))
      (node (ref "P5") (pin "11") (pinfunction "11_11") (pintype "passive"))
      (node (ref "P5") (pin "13") (pinfunction "13_13") (pintype "passive"))
      (node (ref "P5") (pin "3") (pinfunction "3_3") (pintype "passive"))
      (node (ref "P5") (pin "5") (pinfunction "5_5") (pintype "passive"))
      (node (ref "P5") (pin "7") (pinfunction "7_7") (pintype "passive"))
      (node (ref "P5") (pin "9") (pinfunction "9_9") (pintype "passive"))
      (node (ref "P6") (pin "10") (pinfunction "10_10") (pintype "passive"))
      (node (ref "P6") (pin "12") (pinfunction "12_12") (pintype "passive"))
      (node (ref "P6") (pin "14") (pinfunction "14_14") (pintype "passive"))
      (node (ref "P6") (pin "16") (pinfunction "16_16") (pintype "passive"))
      (node (ref "P6") (pin "18") (pinfunction "18_18") (pintype "passive"))
      (node (ref "P6") (pin "20") (pinfunction "20_20") (pintype "passive"))
      (node (ref "P6") (pin "4") (pinfunction "4_4") (pintype "passive"))
      (node (ref "P6") (pin "6") (pinfunction "6_6") (pintype "passive"))
      (node (ref "P6") (pin "8") (pinfunction "8_8") (pintype "passive"))
      (node (ref "P8") (pin "2") (pinfunction "Y_2") (pintype "passive"))
    )
    (net (code "237") (name "GND_ETH") (class "Default")
      (node (ref "CN1") (pin "12") (pinfunction "D3_12") (pintype "passive"))
      (node (ref "CN1") (pin "9") (pinfunction "D2_9") (pintype "passive"))
    )
    (net (code "238") (name "unconnected-(CN1-Pad4)") (class "Default")
      (node (ref "CN1") (pin "4") (pinfunction "4_4") (pintype "passive"))
    )
    (net (code "239") (name "unconnected-(CN1-Pad5)") (class "Default")
      (node (ref "CN1") (pin "5") (pinfunction "5_5") (pintype "passive"))
    )
    (net (code "240") (name "unconnected-(CN1-Pad7)") (class "Default")
      (node (ref "CN1") (pin "7") (pinfunction "7_7") (pintype "passive"))
    )
    (net (code "241") (name "unconnected-(CN1-Pad8)") (class "Default")
      (node (ref "CN1") (pin "8") (pinfunction "8_8") (pintype "passive"))
    )
    (net (code "242") (name "unconnected-(J2-Pad5)") (class "Default")
      (node (ref "J2") (pin "5") (pinfunction "5_5") (pintype "passive"))
    )
    (net (code "243") (name "unconnected-(J2-Pad7)") (class "Default")
      (node (ref "J2") (pin "7") (pinfunction "7_7") (pintype "passive"))
    )
    (net (code "244") (name "unconnected-(P5-Pad12)") (class "Default")
      (node (ref "P5") (pin "12") (pinfunction "12_12") (pintype "passive+no_connect"))
    )
    (net (code "245") (name "unconnected-(P5-Pad14)") (class "Default")
      (node (ref "P5") (pin "14") (pinfunction "14_14") (pintype "passive+no_connect"))
    )
    (net (code "246") (name "unconnected-(P6-Pad17)") (class "Default")
      (node (ref "P6") (pin "17") (pinfunction "17_17") (pintype "passive+no_connect"))
    )
    (net (code "247") (name "unconnected-(P6-Pad19)") (class "Default")
      (node (ref "P6") (pin "19") (pinfunction "19_19") (pintype "passive+no_connect"))
    )
  )
)
